# 006P-5V-3V3Supply.net
KiCad netlist of a schematic drawn in EAGLE
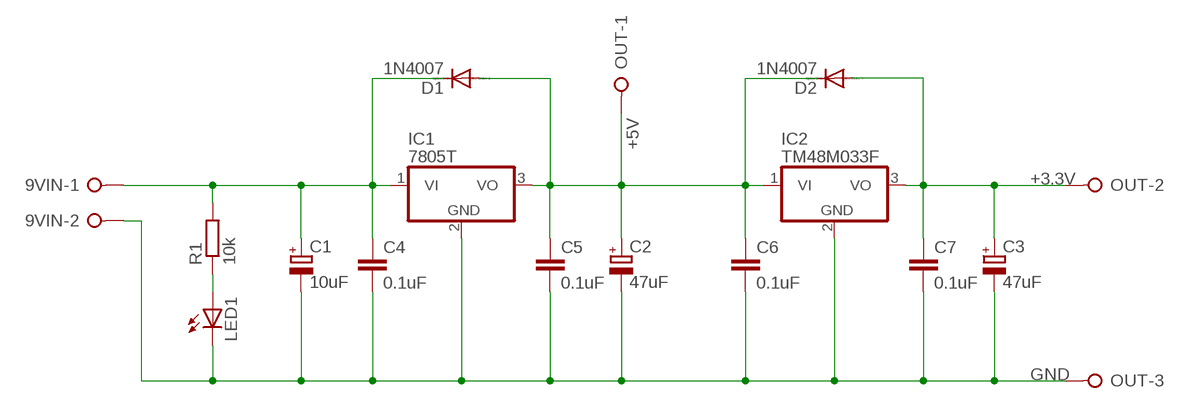
[diagram p0: schematic, sheet 1]

(export (version "E")
  (design (tool "Eeschema 10.0.6"))
  (components
    (comp (ref "9VIN")
      (value "W237-02P")
      (footprint "eagle-import:W237-132")
      (libsource (lib "eagle-import") (part "W237-02P"))
    )
    (comp (ref "C1")
      (value "10uF")
      (footprint "eagle-import:TT2D4L")
      (libsource (lib "eagle-import") (part "CPOL-EUTT2D4L"))
    )
    (comp (ref "C2")
      (value "47uF")
      (footprint "eagle-import:TT2D5L")
      (libsource (lib "eagle-import") (part "CPOL-EUTT2D5L"))
    )
    (comp (ref "C3")
      (value "47uF")
      (footprint "eagle-import:TT2D5L")
      (libsource (lib "eagle-import") (part "CPOL-EUTT2D5L"))
    )
    (comp (ref "C4")
      (value "0.1uF")
      (footprint "eagle-import:C025-024X044")
      (libsource (lib "eagle-import") (part "C-EU025-024X044"))
    )
    (comp (ref "C5")
      (value "0.1uF")
      (footprint "eagle-import:C025-024X044")
      (libsource (lib "eagle-import") (part "C-EU025-024X044"))
    )
    (comp (ref "C6")
      (value "0.1uF")
      (footprint "eagle-import:C025-024X044")
      (libsource (lib "eagle-import") (part "C-EU025-024X044"))
    )
    (comp (ref "C7")
      (value "0.1uF")
      (footprint "eagle-import:C025-024X044")
      (libsource (lib "eagle-import") (part "C-EU025-024X044"))
    )
    (comp (ref "D1")
      (value "1N4007")
      (footprint "eagle-import:DO41-10")
      (libsource (lib "eagle-import") (part "1N4004"))
    )
    (comp (ref "D2")
      (value "1N4007")
      (footprint "eagle-import:DO41-10")
      (libsource (lib "eagle-import") (part "1N4004"))
    )
    (comp (ref "IC1")
      (value "7805T")
      (footprint "eagle-import:TO220H")
      (libsource (lib "eagle-import") (part "78T05"))
    )
    (comp (ref "IC2")
      (value "TM48M033F")
      (footprint "eagle-import:TO220V")
      (libsource (lib "eagle-import") (part "78TV05"))
    )
    (comp (ref "LED1")
      (value "LED3MM")
      (footprint "eagle-import:LED3MM")
      (libsource (lib "eagle-import") (part "LED3MM"))
    )
    (comp (ref "OUT")
      (value "W237-03P")
      (footprint "eagle-import:W237-133")
      (libsource (lib "eagle-import") (part "W237-03P"))
    )
    (comp (ref "R1")
      (value "10k")
      (footprint "eagle-import:0207_7")
      (libsource (lib "eagle-import") (part "R-EU_0207/7"))
    )
  )
  (nets
    (net (code "1") (name "/+3.3V") (class "Default")
      (node (ref "C3") (pin "+") (pinfunction "+_+") (pintype "passive"))
      (node (ref "C7") (pin "1") (pinfunction "1_1") (pintype "passive"))
      (node (ref "D2") (pin "A") (pinfunction "A_A") (pintype "passive"))
      (node (ref "IC2") (pin "3") (pinfunction "VO_3") (pintype "passive"))
      (node (ref "OUT") (pin "2") (pinfunction "KL_2") (pintype "passive"))
    )
    (net (code "2") (name "/+5V") (class "Default")
      (node (ref "C2") (pin "+") (pinfunction "+_+") (pintype "passive"))
      (node (ref "C5") (pin "1") (pinfunction "1_1") (pintype "passive"))
      (node (ref "C6") (pin "1") (pinfunction "1_1") (pintype "passive"))
      (node (ref "D1") (pin "A") (pinfunction "A_A") (pintype "passive"))
      (node (ref "D2") (pin "C") (pinfunction "C_C") (pintype "passive"))
      (node (ref "IC1") (pin "3") (pinfunction "VO_3") (pintype "passive"))
      (node (ref "IC2") (pin "1") (pinfunction "VI_1") (pintype "input"))
      (node (ref "OUT") (pin "1") (pinfunction "KL_1") (pintype "passive"))
    )
    (net (code "3") (name "/GND") (class "Default")
      (node (ref "9VIN") (pin "2") (pinfunction "KL_2") (pintype "passive"))
      (node (ref "C1") (pin "-") (pinfunction "-_-") (pintype "passive"))
      (node (ref "C2") (pin "-") (pinfunction "-_-") (pintype "passive"))
      (node (ref "C3") (pin "-") (pinfunction "-_-") (pintype "passive"))
      (node (ref "C4") (pin "2") (pinfunction "2_2") (pintype "passive"))
      (node (ref "C5") (pin "2") (pinfunction "2_2") (pintype "passive"))
      (node (ref "C6") (pin "2") (pinfunction "2_2") (pintype "passive"))
      (node (ref "C7") (pin "2") (pinfunction "2_2") (pintype "passive"))
      (node (ref "IC1") (pin "2") (pinfunction "GND_2") (pintype "passive"))
      (node (ref "IC2") (pin "2") (pinfunction "GND_2") (pintype "passive"))
      (node (ref "LED1") (pin "K") (pinfunction "C_K") (pintype "passive"))
      (node (ref "OUT") (pin "3") (pinfunction "KL_3") (pintype "passive"))
    )
    (net (code "4") (name "Net-(9VINA-KL)") (class "Default")
      (node (ref "9VIN") (pin "1") (pinfunction "KL_1") (pintype "passive"))
      (node (ref "C1") (pin "+") (pinfunction "+_+") (pintype "passive"))
      (node (ref "C4") (pin "1") (pinfunction "1_1") (pintype "passive"))
      (node (ref "D1") (pin "C") (pinfunction "C_C") (pintype "passive"))
      (node (ref "IC1") (pin "1") (pinfunction "VI_1") (pintype "input"))
      (node (ref "R1") (pin "2") (pinfunction "2_2") (pintype "passive"))
    )
    (net (code "5") (name "Net-(LED1-PadA)") (class "Default")
      (node (ref "LED1") (pin "A") (pinfunction "A_A") (pintype "passive"))
      (node (ref "R1") (pin "1") (pinfunction "1_1") (pintype "passive"))
    )
  )
)
